# Sheet1.net
KiCad netlist of a schematic drawn in Altium Designer
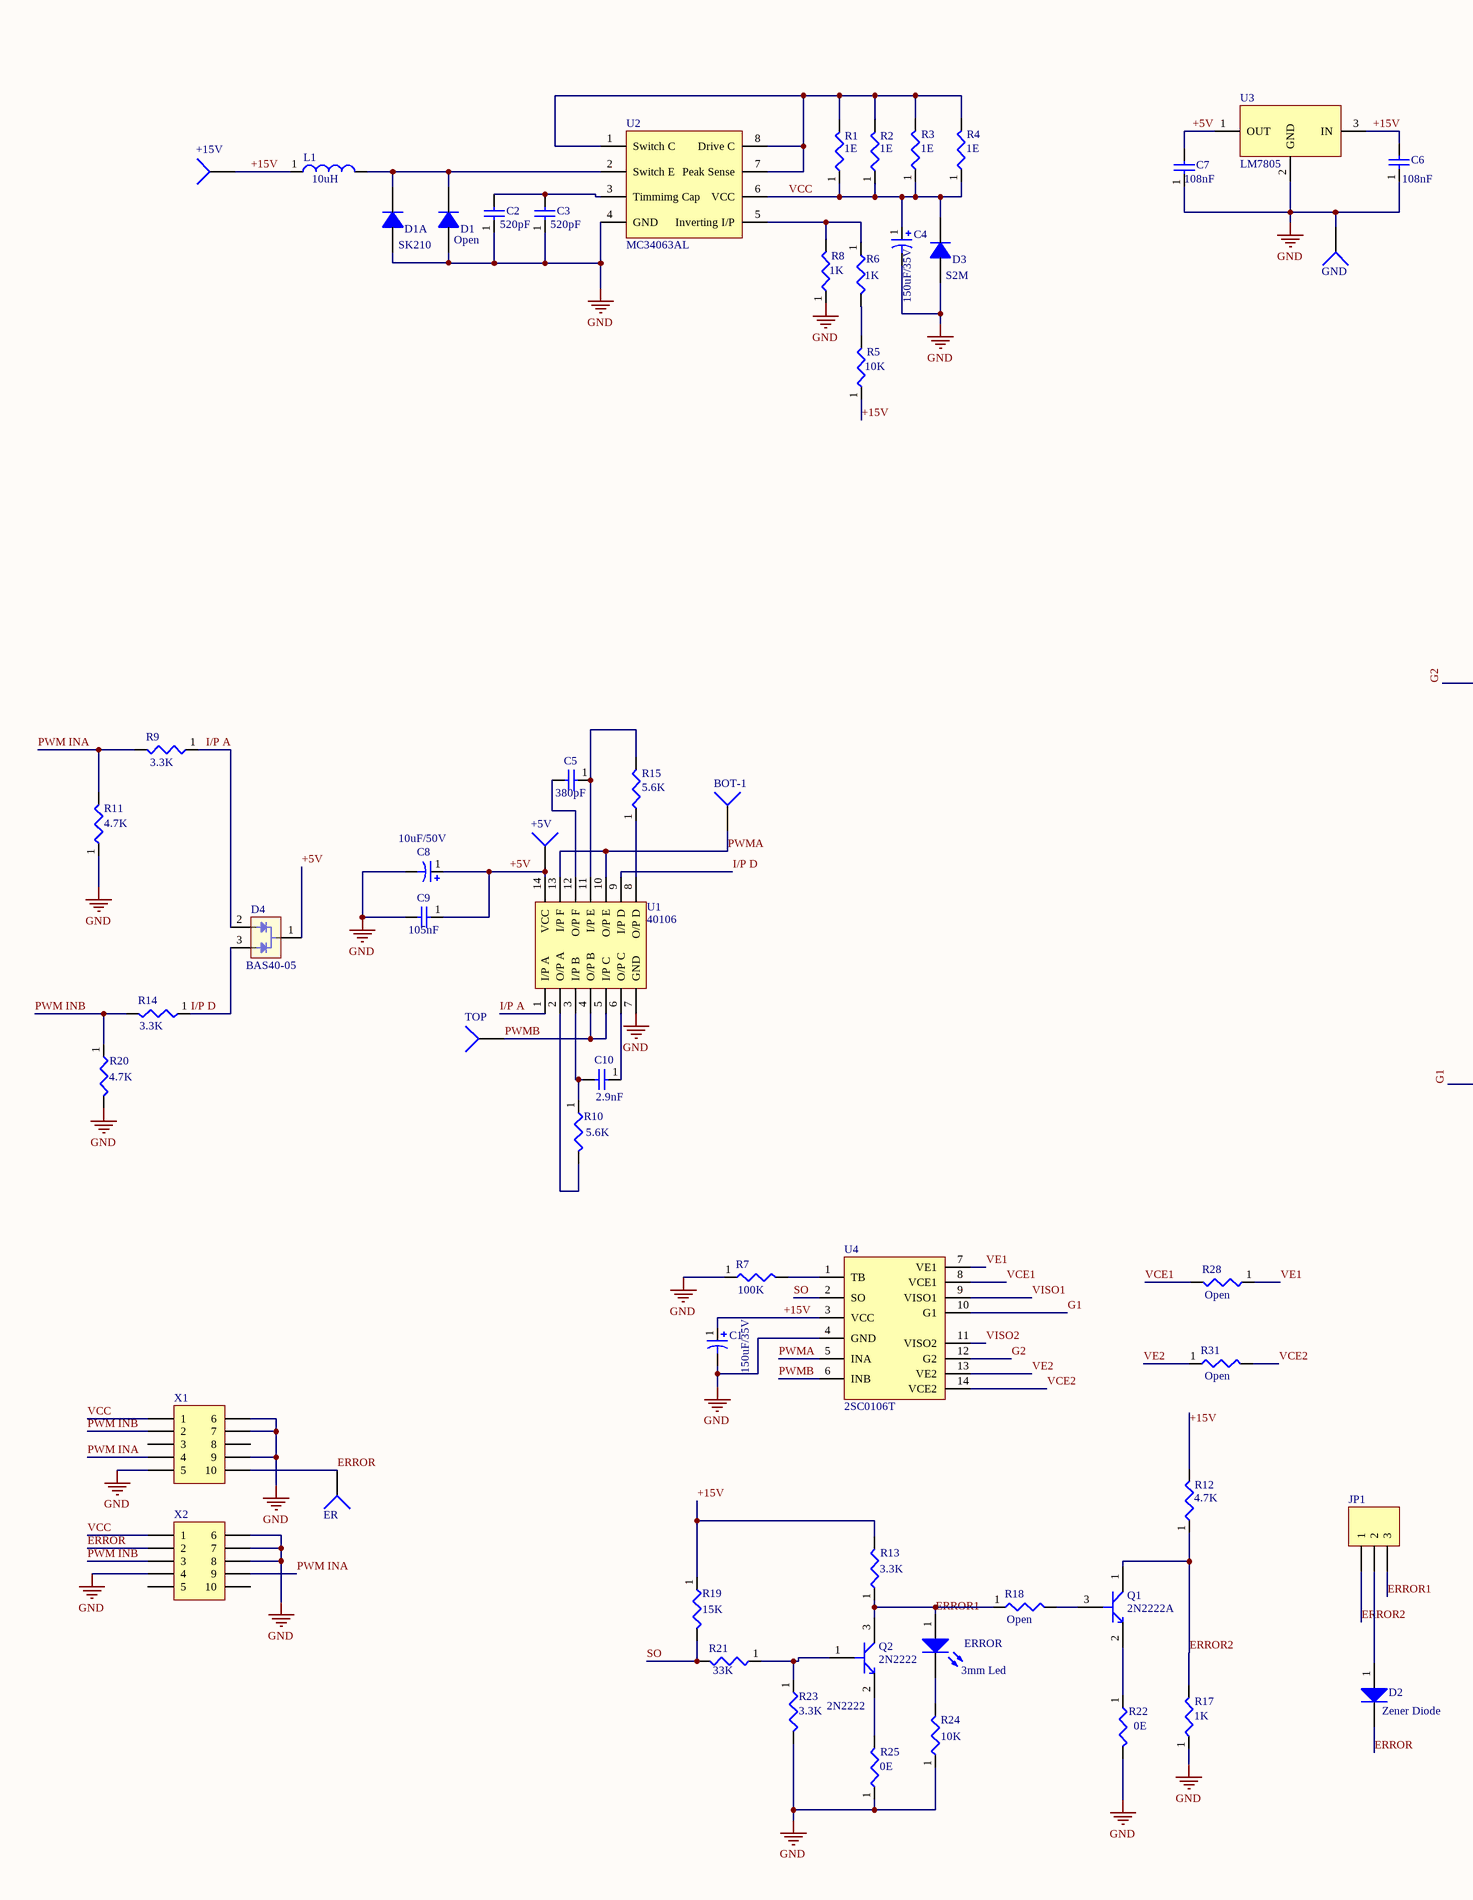
[diagram p0: Sheet1.SchDoc, left]
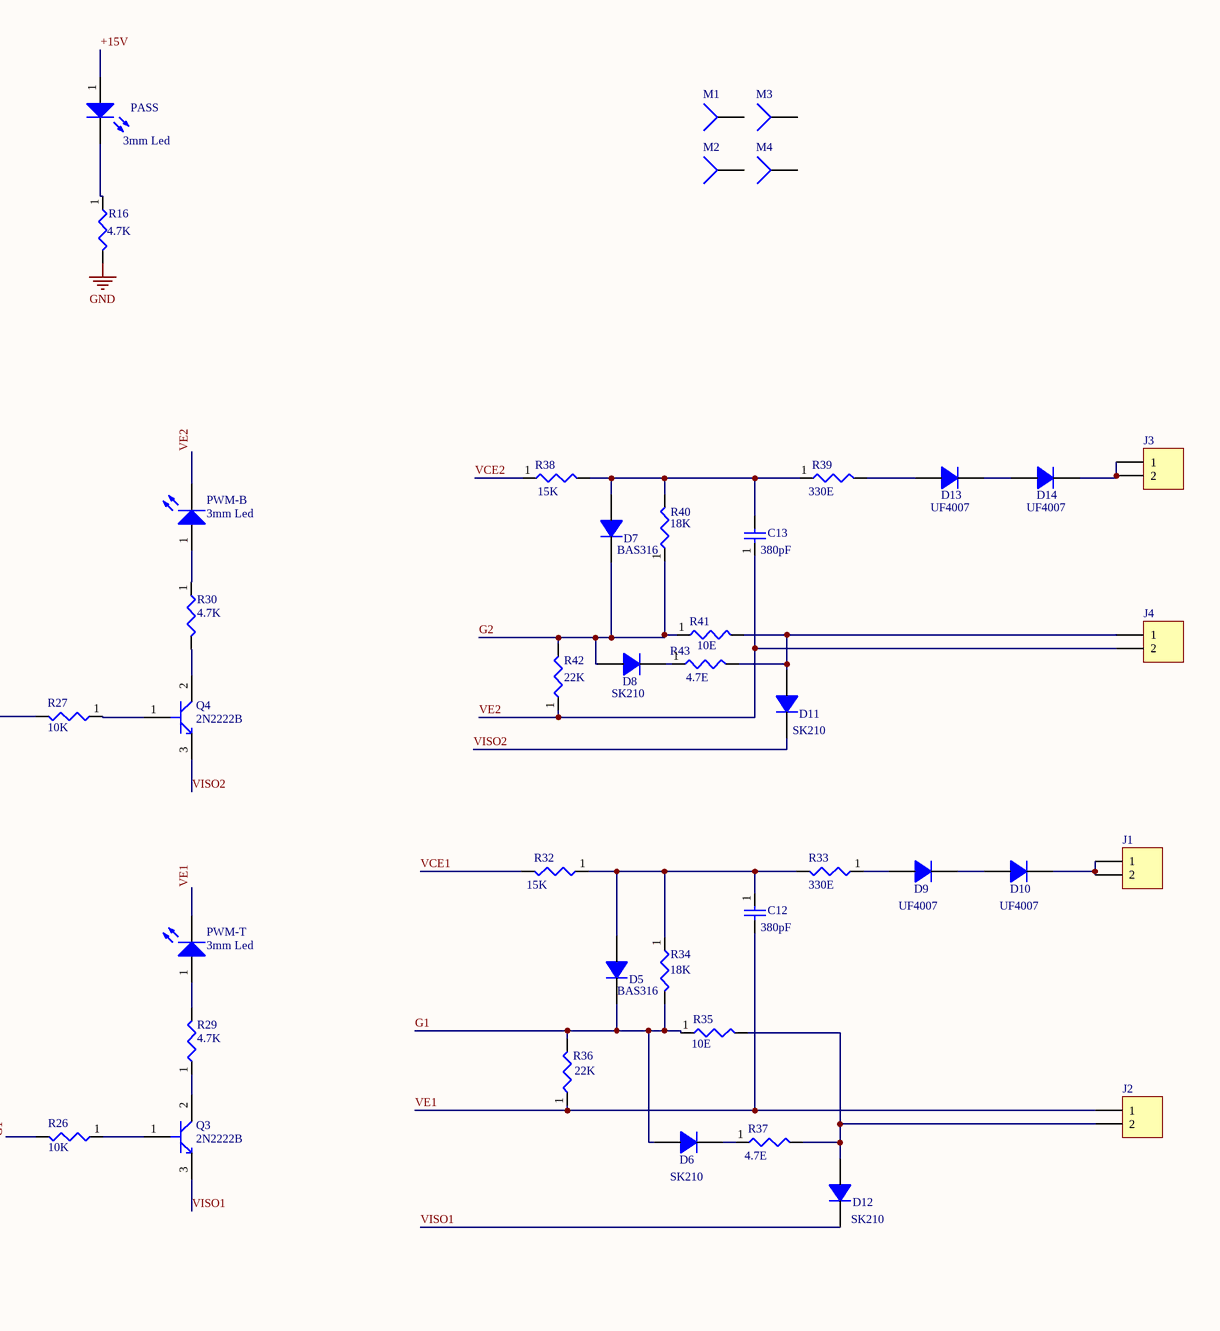
[diagram p1: Sheet1.SchDoc, right]

(export (version "E")
  (design (tool "Eeschema 10.0.6"))
  (components
    (comp (ref "+5V")
      (value "Socket")
      (footprint "tp")
      (fields (field (name "PUBLISHER") "Altium Limited"))
      (libsource (lib "Miscellaneous Connectors") (part "Socket"))
    )
    (comp (ref "+15V")
      (value "Socket")
      (footprint "tp")
      (fields (field (name "PUBLISHER") "Altium Limited"))
      (libsource (lib "Miscellaneous Connectors") (part "Socket"))
    )
    (comp (ref "BOT-1")
      (value "Socket")
      (footprint "tp")
      (fields (field (name "PUBLISHER") "Altium Limited"))
      (libsource (lib "Miscellaneous Connectors") (part "Socket"))
    )
    (comp (ref "C1")
      (value "150uF/35V")
      (footprint "10 mm Elco")
      (description "Polarized Capacitor (Radial)")
      (fields (field (name "Comment") "Cap Pol1") (field (name "PUBLISHER") "Altium Limited"))
      (libsource (lib "Miscellaneous Devices") (part "Cap Pol1"))
    )
    (comp (ref "C2")
      (value "520pF")
      (footprint "RESC0805-1206")
      (description "Capacitor")
      (fields (field (name "Comment") "Cap") (field (name "PUBLISHER") "Altium Limited"))
      (libsource (lib "Miscellaneous Devices") (part "Cap"))
    )
    (comp (ref "C3")
      (value "520pF")
      (footprint "RESC0805-1206")
      (description "Capacitor")
      (fields (field (name "Comment") "Cap") (field (name "PUBLISHER") "Altium Limited"))
      (libsource (lib "Miscellaneous Devices") (part "Cap"))
    )
    (comp (ref "C4")
      (value "150uF/35V")
      (footprint "10 mm Elco")
      (description "Polarized Capacitor (Radial)")
      (fields (field (name "Comment") "Cap Pol1") (field (name "PUBLISHER") "Altium Limited"))
      (libsource (lib "Miscellaneous Devices") (part "Cap Pol1"))
    )
    (comp (ref "C5")
      (value "380pF")
      (footprint "RESC0805-1206")
      (description "Capacitor")
      (fields (field (name "Comment") "Cap") (field (name "PUBLISHER") "Altium Limited"))
      (libsource (lib "Miscellaneous Devices") (part "Cap"))
    )
    (comp (ref "C6")
      (value "108nF")
      (footprint "RESC0805-1206")
      (description "Capacitor")
      (fields (field (name "Comment") "Cap") (field (name "PUBLISHER") "Altium Limited"))
      (libsource (lib "Miscellaneous Devices") (part "Cap"))
    )
    (comp (ref "C7")
      (value "108nF")
      (footprint "RESC0805-1206")
      (description "Capacitor")
      (fields (field (name "Comment") "Cap") (field (name "PUBLISHER") "Altium Limited"))
      (libsource (lib "Miscellaneous Devices") (part "Cap"))
    )
    (comp (ref "C8")
      (value "10uF/50V")
      (footprint "elco cap")
      (description "Polarized Capacitor (Radial)")
      (fields (field (name "Comment") "Cap Pol1") (field (name "PUBLISHER") "Altium Limited"))
      (libsource (lib "Miscellaneous Devices") (part "Cap Pol1"))
    )
    (comp (ref "C9")
      (value "105nF")
      (footprint "RESC0805-1206")
      (description "Capacitor")
      (fields (field (name "Comment") "Cap") (field (name "PUBLISHER") "Altium Limited"))
      (libsource (lib "Miscellaneous Devices") (part "Cap"))
    )
    (comp (ref "C10")
      (value "2.9nF")
      (footprint "RESC0805-1206")
      (description "Capacitor")
      (fields (field (name "Comment") "Cap") (field (name "PUBLISHER") "Altium Limited"))
      (libsource (lib "Miscellaneous Devices") (part "Cap"))
    )
    (comp (ref "C12")
      (value "380pF")
      (footprint "RESC0805-1206")
      (description "Capacitor")
      (fields (field (name "Comment") "Cap") (field (name "PUBLISHER") "Altium Limited"))
      (libsource (lib "Miscellaneous Devices") (part "Cap"))
    )
    (comp (ref "C13")
      (value "380pF")
      (footprint "RESC0805-1206")
      (description "Capacitor")
      (fields (field (name "Comment") "Cap") (field (name "PUBLISHER") "Altium Limited"))
      (libsource (lib "Miscellaneous Devices") (part "Cap"))
    )
    (comp (ref "D1")
      (value "Open")
      (footprint "Diode")
      (fields (field (name "Comment") "Diode"))
      (libsource (lib "Schlib1") (part "Diode"))
    )
    (comp (ref "D1A")
      (value "SK210")
      (footprint "smb")
      (fields (field (name "Comment") "Diode"))
      (libsource (lib "Schlib1") (part "Diode"))
    )
    (comp (ref "D2")
      (value "Zener Diode")
      (footprint "1206 diode")
      (description "Default Diode")
      (fields (field (name "Comment") "Diode") (field (name "PUBLISHER") "Altium Limited"))
      (libsource (lib "Miscellaneous Devices") (part "Diode"))
    )
    (comp (ref "D3")
      (value "S2M")
      (footprint "smb")
      (fields (field (name "Comment") "Diode"))
      (libsource (lib "Schlib1") (part "Diode"))
    )
    (comp (ref "D4") (value "BAS40-05") (footprint "SOT23_N") (libsource (lib "Schlib1") (part "BAS40-05")))
    (comp (ref "D5")
      (value "BAS316")
      (footprint "smd diode")
      (fields (field (name "Comment") "Diode"))
      (libsource (lib "Schlib1") (part "Diode"))
    )
    (comp (ref "D6")
      (value "SK210")
      (footprint "smb")
      (fields (field (name "Comment") "Diode"))
      (libsource (lib "Schlib1") (part "Diode"))
    )
    (comp (ref "D7")
      (value "BAS316")
      (footprint "smd diode")
      (fields (field (name "Comment") "Diode"))
      (libsource (lib "Schlib1") (part "Diode"))
    )
    (comp (ref "D8")
      (value "SK210")
      (footprint "smb")
      (fields (field (name "Comment") "Diode"))
      (libsource (lib "Schlib1") (part "Diode"))
    )
    (comp (ref "D9")
      (value "UF4007")
      (footprint "Diode")
      (fields (field (name "Comment") "Diode"))
      (libsource (lib "Schlib1") (part "Diode"))
    )
    (comp (ref "D10")
      (value "UF4007")
      (footprint "Diode")
      (fields (field (name "Comment") "Diode"))
      (libsource (lib "Schlib1") (part "Diode"))
    )
    (comp (ref "D11")
      (value "SK210")
      (footprint "smb")
      (fields (field (name "Comment") "Diode"))
      (libsource (lib "Schlib1") (part "Diode"))
    )
    (comp (ref "D12")
      (value "SK210")
      (footprint "smb")
      (fields (field (name "Comment") "Diode"))
      (libsource (lib "Schlib1") (part "Diode"))
    )
    (comp (ref "D13")
      (value "UF4007")
      (footprint "Diode")
      (fields (field (name "Comment") "Diode"))
      (libsource (lib "Schlib1") (part "Diode"))
    )
    (comp (ref "D14")
      (value "UF4007")
      (footprint "Diode")
      (fields (field (name "Comment") "Diode"))
      (libsource (lib "Schlib1") (part "Diode"))
    )
    (comp (ref "ER")
      (value "Socket")
      (footprint "tp")
      (fields (field (name "PUBLISHER") "Altium Limited"))
      (libsource (lib "Miscellaneous Connectors") (part "Socket"))
    )
    (comp (ref "ERROR")
      (value "3mm Led")
      (footprint "led")
      (description "Typical INFRARED GaAs LED")
      (fields (field (name "Comment") "LED0") (field (name "PUBLISHER") "Altium Limited"))
      (libsource (lib "Miscellaneous Devices") (part "LED0"))
    )
    (comp (ref "GND")
      (value "Socket")
      (footprint "tp")
      (fields (field (name "PUBLISHER") "Altium Limited"))
      (libsource (lib "Miscellaneous Connectors") (part "Socket"))
    )
    (comp (ref "J1")
      (value "Header 2")
      (footprint "2 pin con")
      (description "Header, 2-Pin")
      (fields (field (name "PUBLISHER") "Altium Limited"))
      (libsource (lib "Miscellaneous Connectors") (part "Header 2"))
    )
    (comp (ref "J2")
      (value "Header 2")
      (footprint "2 pin con")
      (description "Header, 2-Pin")
      (fields (field (name "PUBLISHER") "Altium Limited"))
      (libsource (lib "Miscellaneous Connectors") (part "Header 2"))
    )
    (comp (ref "J3")
      (value "Header 2")
      (footprint "2 pin con")
      (description "Header, 2-Pin")
      (fields (field (name "PUBLISHER") "Altium Limited"))
      (libsource (lib "Miscellaneous Connectors") (part "Header 2"))
    )
    (comp (ref "J4")
      (value "Header 2")
      (footprint "2 pin con")
      (description "Header, 2-Pin")
      (fields (field (name "PUBLISHER") "Altium Limited"))
      (libsource (lib "Miscellaneous Connectors") (part "Header 2"))
    )
    (comp (ref "JP1")
      (value "Header 3")
      (footprint "3 pin con")
      (description "Header, 3-Pin")
      (fields (field (name "PUBLISHER") "Altium Limited"))
      (libsource (lib "Miscellaneous Connectors") (part "Header 3"))
    )
    (comp (ref "L1")
      (value "10uH")
      (footprint "INDUCTOR")
      (description "Inductor")
      (fields (field (name "PUBLISHER") "Altium Limited"))
      (libsource (lib "Miscellaneous Devices") (part "Inductor"))
    )
    (comp (ref "M1")
      (value "Socket")
      (footprint "Mounting Hole")
      (fields (field (name "PUBLISHER") "Altium Limited"))
      (libsource (lib "Miscellaneous Connectors") (part "Socket"))
    )
    (comp (ref "M2")
      (value "Socket")
      (footprint "Mounting Hole")
      (fields (field (name "PUBLISHER") "Altium Limited"))
      (libsource (lib "Miscellaneous Connectors") (part "Socket"))
    )
    (comp (ref "M3")
      (value "Socket")
      (footprint "Mounting Hole")
      (fields (field (name "PUBLISHER") "Altium Limited"))
      (libsource (lib "Miscellaneous Connectors") (part "Socket"))
    )
    (comp (ref "M4")
      (value "Socket")
      (footprint "Mounting Hole")
      (fields (field (name "PUBLISHER") "Altium Limited"))
      (libsource (lib "Miscellaneous Connectors") (part "Socket"))
    )
    (comp (ref "PASS")
      (value "3mm Led")
      (footprint "led")
      (description "Typical INFRARED GaAs LED")
      (fields (field (name "Comment") "LED0") (field (name "PUBLISHER") "Altium Limited"))
      (libsource (lib "Miscellaneous Devices") (part "LED0"))
    )
    (comp (ref "PWM-B")
      (value "3mm Led")
      (footprint "led")
      (description "Typical INFRARED GaAs LED")
      (fields (field (name "Comment") "LED0") (field (name "PUBLISHER") "Altium Limited"))
      (libsource (lib "Miscellaneous Devices") (part "LED0"))
    )
    (comp (ref "PWM-T")
      (value "3mm Led")
      (footprint "led")
      (description "Typical INFRARED GaAs LED")
      (fields (field (name "Comment") "LED0") (field (name "PUBLISHER") "Altium Limited"))
      (libsource (lib "Miscellaneous Devices") (part "LED0"))
    )
    (comp (ref "Q1") (value "2N2222A") (footprint "SOT23_N") (libsource (lib "Schlib1") (part "2N2222A")))
    (comp (ref "Q2")
      (value "2N2222")
      (footprint "SOT-23_N")
      (fields (field (name "ALTIUM_VALUE") "2N2222"))
      (libsource (lib "Schlib1") (part "2N2222"))
    )
    (comp (ref "Q3") (value "2N2222B") (footprint "SOT-23_N") (libsource (lib "Schlib1") (part "2N2222B")))
    (comp (ref "Q4") (value "2N2222B") (footprint "SOT-23_N") (libsource (lib "Schlib1") (part "2N2222B")))
    (comp (ref "R1")
      (value "1E")
      (footprint "RESC0805-1206")
      (description "Resistor")
      (fields (field (name "Comment") "Res3") (field (name "PUBLISHER") "Altium Limited"))
      (libsource (lib "Miscellaneous Devices") (part "Res3"))
    )
    (comp (ref "R2")
      (value "1E")
      (footprint "RESC0805-1206")
      (description "Resistor")
      (fields (field (name "Comment") "Res3") (field (name "PUBLISHER") "Altium Limited"))
      (libsource (lib "Miscellaneous Devices") (part "Res3"))
    )
    (comp (ref "R3")
      (value "1E")
      (footprint "RESC0805-1206")
      (description "Resistor")
      (fields (field (name "Comment") "Res3") (field (name "PUBLISHER") "Altium Limited"))
      (libsource (lib "Miscellaneous Devices") (part "Res3"))
    )
    (comp (ref "R4")
      (value "1E")
      (footprint "RESC0805-1206")
      (description "Resistor")
      (fields (field (name "Comment") "Res3") (field (name "PUBLISHER") "Altium Limited"))
      (libsource (lib "Miscellaneous Devices") (part "Res3"))
    )
    (comp (ref "R5")
      (value "10K")
      (footprint "RESC0805-1206")
      (description "Resistor")
      (fields (field (name "Comment") "Res3") (field (name "PUBLISHER") "Altium Limited"))
      (libsource (lib "Miscellaneous Devices") (part "Res3"))
    )
    (comp (ref "R6")
      (value "1K")
      (footprint "RESC0805-1206")
      (description "Resistor")
      (fields (field (name "Comment") "Res3") (field (name "PUBLISHER") "Altium Limited"))
      (libsource (lib "Miscellaneous Devices") (part "Res3"))
    )
    (comp (ref "R7")
      (value "100K")
      (footprint "RESC0805-1206")
      (description "Resistor")
      (fields (field (name "Comment") "Res3") (field (name "PUBLISHER") "Altium Limited"))
      (libsource (lib "Miscellaneous Devices") (part "Res3"))
    )
    (comp (ref "R8")
      (value "1K")
      (footprint "RESC0805-1206")
      (description "Resistor")
      (fields (field (name "Comment") "Res3") (field (name "PUBLISHER") "Altium Limited"))
      (libsource (lib "Miscellaneous Devices") (part "Res3"))
    )
    (comp (ref "R9")
      (value "3.3K")
      (footprint "RESC0805-1206")
      (description "Resistor")
      (fields (field (name "Comment") "Res3") (field (name "PUBLISHER") "Altium Limited"))
      (libsource (lib "Miscellaneous Devices") (part "Res3"))
    )
    (comp (ref "R10")
      (value "5.6K")
      (footprint "RESC0805-1206")
      (description "Resistor")
      (fields (field (name "Comment") "Res3") (field (name "PUBLISHER") "Altium Limited"))
      (libsource (lib "Miscellaneous Devices") (part "Res3"))
    )
    (comp (ref "R11")
      (value "4.7K")
      (footprint "RESC0805-1206")
      (description "Resistor")
      (fields (field (name "Comment") "Res3") (field (name "PUBLISHER") "Altium Limited"))
      (libsource (lib "Miscellaneous Devices") (part "Res3"))
    )
    (comp (ref "R12")
      (value "4.7K")
      (footprint "RESC0805-1206")
      (description "Resistor")
      (fields (field (name "Comment") "Res3") (field (name "PUBLISHER") "Altium Limited"))
      (libsource (lib "Miscellaneous Devices") (part "Res3"))
    )
    (comp (ref "R13")
      (value "3.3K")
      (footprint "RESC0805-1206")
      (description "Resistor")
      (fields (field (name "Comment") "Res3") (field (name "PUBLISHER") "Altium Limited"))
      (libsource (lib "Miscellaneous Devices") (part "Res3"))
    )
    (comp (ref "R14")
      (value "3.3K")
      (footprint "RESC0805-1206")
      (description "Resistor")
      (fields (field (name "Comment") "Res3") (field (name "PUBLISHER") "Altium Limited"))
      (libsource (lib "Miscellaneous Devices") (part "Res3"))
    )
    (comp (ref "R15")
      (value "5.6K")
      (footprint "RESC0805-1206")
      (description "Resistor")
      (fields (field (name "Comment") "Res3") (field (name "PUBLISHER") "Altium Limited"))
      (libsource (lib "Miscellaneous Devices") (part "Res3"))
    )
    (comp (ref "R16")
      (value "4.7K")
      (footprint "RESC0805-1206")
      (description "Resistor")
      (fields (field (name "Comment") "Res3") (field (name "PUBLISHER") "Altium Limited"))
      (libsource (lib "Miscellaneous Devices") (part "Res3"))
    )
    (comp (ref "R17")
      (value "1K")
      (footprint "RESC0805-1206")
      (description "Resistor")
      (fields (field (name "Comment") "Res3") (field (name "PUBLISHER") "Altium Limited"))
      (libsource (lib "Miscellaneous Devices") (part "Res3"))
    )
    (comp (ref "R18")
      (value "Open")
      (footprint "RESC0805-1206")
      (description "Resistor")
      (fields (field (name "Comment") "Res3") (field (name "PUBLISHER") "Altium Limited"))
      (libsource (lib "Miscellaneous Devices") (part "Res3"))
    )
    (comp (ref "R19")
      (value "15K")
      (footprint "RESC0805-1206")
      (description "Resistor")
      (fields (field (name "Comment") "Res3") (field (name "PUBLISHER") "Altium Limited"))
      (libsource (lib "Miscellaneous Devices") (part "Res3"))
    )
    (comp (ref "R20")
      (value "4.7K")
      (footprint "RESC0805-1206")
      (description "Resistor")
      (fields (field (name "Comment") "Res3") (field (name "PUBLISHER") "Altium Limited"))
      (libsource (lib "Miscellaneous Devices") (part "Res3"))
    )
    (comp (ref "R21")
      (value "33K")
      (footprint "RESC0805-1206")
      (description "Resistor")
      (fields (field (name "Comment") "Res3") (field (name "PUBLISHER") "Altium Limited"))
      (libsource (lib "Miscellaneous Devices") (part "Res3"))
    )
    (comp (ref "R22")
      (value "0E")
      (footprint "RESC0805-1206")
      (description "Resistor")
      (fields (field (name "Comment") "Res3") (field (name "PUBLISHER") "Altium Limited"))
      (libsource (lib "Miscellaneous Devices") (part "Res3"))
    )
    (comp (ref "R23")
      (value "3.3K")
      (footprint "RESC0805-1206")
      (description "Resistor")
      (fields (field (name "Comment") "Res3") (field (name "PUBLISHER") "Altium Limited"))
      (libsource (lib "Miscellaneous Devices") (part "Res3"))
    )
    (comp (ref "R24")
      (value "10K")
      (footprint "RESC0805-1206")
      (description "Resistor")
      (fields (field (name "Comment") "Res3") (field (name "PUBLISHER") "Altium Limited"))
      (libsource (lib "Miscellaneous Devices") (part "Res3"))
    )
    (comp (ref "R25")
      (value "0E")
      (footprint "RESC0805-1206")
      (description "Resistor")
      (fields (field (name "Comment") "Res3") (field (name "PUBLISHER") "Altium Limited"))
      (libsource (lib "Miscellaneous Devices") (part "Res3"))
    )
    (comp (ref "R26")
      (value "10K")
      (footprint "RESC0805-1206")
      (description "Resistor")
      (fields (field (name "Comment") "Res3") (field (name "PUBLISHER") "Altium Limited"))
      (libsource (lib "Miscellaneous Devices") (part "Res3"))
    )
    (comp (ref "R27")
      (value "10K")
      (footprint "RESC0805-1206")
      (description "Resistor")
      (fields (field (name "Comment") "Res3") (field (name "PUBLISHER") "Altium Limited"))
      (libsource (lib "Miscellaneous Devices") (part "Res3"))
    )
    (comp (ref "R28")
      (value "Open")
      (footprint "RESC0805-1206")
      (description "Resistor")
      (fields (field (name "Comment") "Res3") (field (name "PUBLISHER") "Altium Limited"))
      (libsource (lib "Miscellaneous Devices") (part "Res3"))
    )
    (comp (ref "R29")
      (value "4.7K")
      (footprint "RESC0805-1206")
      (description "Resistor")
      (fields (field (name "Comment") "Res3") (field (name "PUBLISHER") "Altium Limited"))
      (libsource (lib "Miscellaneous Devices") (part "Res3"))
    )
    (comp (ref "R30")
      (value "4.7K")
      (footprint "RESC0805-1206")
      (description "Resistor")
      (fields (field (name "Comment") "Res3") (field (name "PUBLISHER") "Altium Limited"))
      (libsource (lib "Miscellaneous Devices") (part "Res3"))
    )
    (comp (ref "R31")
      (value "Open")
      (footprint "RESC0805-1206")
      (description "Resistor")
      (fields (field (name "Comment") "Res3") (field (name "PUBLISHER") "Altium Limited"))
      (libsource (lib "Miscellaneous Devices") (part "Res3"))
    )
    (comp (ref "R32")
      (value "15K")
      (footprint "RESC0805-1206")
      (description "Resistor")
      (fields (field (name "Comment") "Res3") (field (name "PUBLISHER") "Altium Limited"))
      (libsource (lib "Miscellaneous Devices") (part "Res3"))
    )
    (comp (ref "R33")
      (value "330E")
      (footprint "RESC0805-1206")
      (description "Resistor")
      (fields (field (name "Comment") "Res3") (field (name "PUBLISHER") "Altium Limited"))
      (libsource (lib "Miscellaneous Devices") (part "Res3"))
    )
    (comp (ref "R34")
      (value "18K")
      (footprint "RESC0805-1206")
      (description "Resistor")
      (fields (field (name "Comment") "Res3") (field (name "PUBLISHER") "Altium Limited"))
      (libsource (lib "Miscellaneous Devices") (part "Res3"))
    )
    (comp (ref "R35")
      (value "10E")
      (footprint "2W Res")
      (description "Resistor")
      (fields (field (name "Comment") "Res3") (field (name "PUBLISHER") "Altium Limited"))
      (libsource (lib "Miscellaneous Devices") (part "Res3"))
    )
    (comp (ref "R36")
      (value "22K")
      (footprint "RESC0805-1206")
      (description "Resistor")
      (fields (field (name "Comment") "Res3") (field (name "PUBLISHER") "Altium Limited"))
      (libsource (lib "Miscellaneous Devices") (part "Res3"))
    )
    (comp (ref "R37")
      (value "4.7E")
      (footprint "2W Res")
      (description "Resistor")
      (fields (field (name "Comment") "Res3") (field (name "PUBLISHER") "Altium Limited"))
      (libsource (lib "Miscellaneous Devices") (part "Res3"))
    )
    (comp (ref "R38")
      (value "15K")
      (footprint "RESC0805-1206")
      (description "Resistor")
      (fields (field (name "Comment") "Res3") (field (name "PUBLISHER") "Altium Limited"))
      (libsource (lib "Miscellaneous Devices") (part "Res3"))
    )
    (comp (ref "R39")
      (value "330E")
      (footprint "RESC0805-1206")
      (description "Resistor")
      (fields (field (name "Comment") "Res3") (field (name "PUBLISHER") "Altium Limited"))
      (libsource (lib "Miscellaneous Devices") (part "Res3"))
    )
    (comp (ref "R40")
      (value "18K")
      (footprint "RESC0805-1206")
      (description "Resistor")
      (fields (field (name "Comment") "Res3") (field (name "PUBLISHER") "Altium Limited"))
      (libsource (lib "Miscellaneous Devices") (part "Res3"))
    )
    (comp (ref "R41")
      (value "10E")
      (footprint "2W Res")
      (description "Resistor")
      (fields (field (name "Comment") "Res3") (field (name "PUBLISHER") "Altium Limited"))
      (libsource (lib "Miscellaneous Devices") (part "Res3"))
    )
    (comp (ref "R42")
      (value "22K")
      (footprint "RESC0805-1206")
      (description "Resistor")
      (fields (field (name "Comment") "Res3") (field (name "PUBLISHER") "Altium Limited"))
      (libsource (lib "Miscellaneous Devices") (part "Res3"))
    )
    (comp (ref "R43")
      (value "4.7E")
      (footprint "2W Res")
      (description "Resistor")
      (fields (field (name "Comment") "Res3") (field (name "PUBLISHER") "Altium Limited"))
      (libsource (lib "Miscellaneous Devices") (part "Res3"))
    )
    (comp (ref "TOP")
      (value "Socket")
      (footprint "tp")
      (fields (field (name "PUBLISHER") "Altium Limited"))
      (libsource (lib "Miscellaneous Connectors") (part "Socket"))
    )
    (comp (ref "U1")
      (value "40106")
      (footprint "sop14")
      (fields (field (name "Comment") "CD40106"))
      (libsource (lib "Schlib1") (part "CD40106"))
    )
    (comp (ref "U2") (value "MC34063AL") (libsource (lib "Schlib1") (part "MC34063AL")))
    (comp (ref "U3") (value "LM7805") (libsource (lib "Schlib1") (part "LM7805")))
    (comp (ref "U4") (value "2SC0106T") (footprint "14 pin ic") (libsource (lib "Schlib1") (part "2SC0106T")))
    (comp (ref "X1")
      (value "Header 5X2A")
      (footprint "10 pin con")
      (description "Header, 5-Pin, Dual row")
      (fields (field (name "PUBLISHER") "Altium Limited"))
      (libsource (lib "Miscellaneous Connectors") (part "Header 5X2A"))
    )
    (comp (ref "X2")
      (value "Header 5X2A")
      (footprint "X2 CON")
      (description "Header, 5-Pin, Dual row")
      (fields (field (name "PUBLISHER") "Altium Limited"))
      (libsource (lib "Miscellaneous Connectors") (part "Header 5X2A"))
    )
  )
  (nets
    (net (code "1") (name "/+5V") (class "Default")
      (node (ref "+5V") (pin "1") (pinfunction "1_1") (pintype "passive"))
      (node (ref "C7") (pin "2") (pinfunction "2_2") (pintype "passive"))
      (node (ref "C8") (pin "1") (pinfunction "1_1") (pintype "passive"))
      (node (ref "C9") (pin "1") (pinfunction "1_1") (pintype "passive"))
      (node (ref "D4") (pin "1") (pinfunction "1_1") (pintype "passive"))
      (node (ref "U1") (pin "14") (pinfunction "VCC_14") (pintype "passive"))
      (node (ref "U3") (pin "1") (pinfunction "OUT_1") (pintype "passive"))
    )
    (net (code "2") (name "/+15V") (class "Default")
      (node (ref "+15V") (pin "1") (pinfunction "1_1") (pintype "passive"))
      (node (ref "C1") (pin "1") (pinfunction "1_1") (pintype "passive"))
      (node (ref "C6") (pin "2") (pinfunction "2_2") (pintype "passive"))
      (node (ref "L1") (pin "1") (pinfunction "1_1") (pintype "passive"))
      (node (ref "PASS") (pin "1") (pinfunction "A_1") (pintype "passive"))
      (node (ref "R12") (pin "2") (pinfunction "2_2") (pintype "passive"))
      (node (ref "R13") (pin "2") (pinfunction "2_2") (pintype "passive"))
      (node (ref "R19") (pin "1") (pinfunction "1_1") (pintype "passive"))
      (node (ref "R5") (pin "1") (pinfunction "1_1") (pintype "passive"))
      (node (ref "U3") (pin "3") (pinfunction "IN_3") (pintype "passive"))
      (node (ref "U4") (pin "3") (pinfunction "VCC_3") (pintype "passive"))
    )
    (net (code "3") (name "/ERROR") (class "Default")
      (node (ref "D2") (pin "2") (pinfunction "K_2") (pintype "passive"))
      (node (ref "ER") (pin "1") (pinfunction "1_1") (pintype "passive"))
      (node (ref "X1") (pin "10") (pinfunction "10_10") (pintype "passive"))
      (node (ref "X2") (pin "2") (pinfunction "2_2") (pintype "passive"))
    )
    (net (code "4") (name "/ERROR1") (class "Default")
      (node (ref "ERROR") (pin "1") (pinfunction "A_1") (pintype "passive"))
      (node (ref "JP1") (pin "3") (pinfunction "3_3") (pintype "passive"))
      (node (ref "Q2") (pin "3") (pinfunction "3_3") (pintype "passive"))
      (node (ref "R13") (pin "1") (pinfunction "1_1") (pintype "passive"))
      (node (ref "R18") (pin "1") (pinfunction "1_1") (pintype "passive"))
    )
    (net (code "5") (name "/ERROR2") (class "Default")
      (node (ref "JP1") (pin "1") (pinfunction "1_1") (pintype "passive"))
      (node (ref "Q1") (pin "1") (pinfunction "1_1") (pintype "passive"))
      (node (ref "R12") (pin "1") (pinfunction "1_1") (pintype "passive"))
      (node (ref "R17") (pin "2") (pinfunction "2_2") (pintype "passive"))
    )
    (net (code "6") (name "/G1") (class "Default")
      (node (ref "D5") (pin "1") (pinfunction "1_1") (pintype "passive"))
      (node (ref "D6") (pin "2") (pinfunction "2_2") (pintype "passive"))
      (node (ref "R26") (pin "2") (pinfunction "2_2") (pintype "passive"))
      (node (ref "R34") (pin "2") (pinfunction "2_2") (pintype "passive"))
      (node (ref "R35") (pin "1") (pinfunction "1_1") (pintype "passive"))
      (node (ref "R36") (pin "2") (pinfunction "2_2") (pintype "passive"))
      (node (ref "U4") (pin "10") (pinfunction "G1_10") (pintype "passive"))
    )
    (net (code "7") (name "/G2") (class "Default")
      (node (ref "D7") (pin "1") (pinfunction "1_1") (pintype "passive"))
      (node (ref "D8") (pin "2") (pinfunction "2_2") (pintype "passive"))
      (node (ref "R27") (pin "2") (pinfunction "2_2") (pintype "passive"))
      (node (ref "R40") (pin "1") (pinfunction "1_1") (pintype "passive"))
      (node (ref "R41") (pin "1") (pinfunction "1_1") (pintype "passive"))
      (node (ref "R42") (pin "2") (pinfunction "2_2") (pintype "passive"))
      (node (ref "U4") (pin "12") (pinfunction "G2_12") (pintype "passive"))
    )
    (net (code "8") (name "/I{slash}P A") (class "Default")
      (node (ref "D4") (pin "2") (pinfunction "2_2") (pintype "passive"))
      (node (ref "R9") (pin "1") (pinfunction "1_1") (pintype "passive"))
      (node (ref "U1") (pin "1") (pinfunction "I/P_A_1") (pintype "passive"))
    )
    (net (code "9") (name "/I{slash}P D") (class "Default")
      (node (ref "D4") (pin "3") (pinfunction "3_3") (pintype "passive"))
      (node (ref "R14") (pin "1") (pinfunction "1_1") (pintype "passive"))
      (node (ref "U1") (pin "9") (pinfunction "I/P_D_9") (pintype "passive"))
    )
    (net (code "10") (name "/PWM INA") (class "Default")
      (node (ref "R11") (pin "2") (pinfunction "2_2") (pintype "passive"))
      (node (ref "R9") (pin "2") (pinfunction "2_2") (pintype "passive"))
      (node (ref "X1") (pin "4") (pinfunction "4_4") (pintype "passive"))
      (node (ref "X2") (pin "9") (pinfunction "9_9") (pintype "passive"))
    )
    (net (code "11") (name "/PWM INB") (class "Default")
      (node (ref "R14") (pin "2") (pinfunction "2_2") (pintype "passive"))
      (node (ref "R20") (pin "1") (pinfunction "1_1") (pintype "passive"))
      (node (ref "X1") (pin "2") (pinfunction "2_2") (pintype "passive"))
      (node (ref "X2") (pin "3") (pinfunction "3_3") (pintype "passive"))
    )
    (net (code "12") (name "/PWMA") (class "Default")
      (node (ref "BOT-1") (pin "1") (pinfunction "1_1") (pintype "passive"))
      (node (ref "U1") (pin "10") (pinfunction "O/P_E_10") (pintype "passive"))
      (node (ref "U1") (pin "13") (pinfunction "I/P_F_13") (pintype "passive"))
      (node (ref "U4") (pin "5") (pinfunction "INA_5") (pintype "passive"))
    )
    (net (code "13") (name "/PWMB") (class "Default")
      (node (ref "TOP") (pin "1") (pinfunction "1_1") (pintype "passive"))
      (node (ref "U1") (pin "4") (pinfunction "O/P_B_4") (pintype "passive"))
      (node (ref "U1") (pin "5") (pinfunction "I/P_C_5") (pintype "passive"))
      (node (ref "U4") (pin "6") (pinfunction "INB_6") (pintype "passive"))
    )
    (net (code "14") (name "/SO") (class "Default")
      (node (ref "R19") (pin "2") (pinfunction "2_2") (pintype "passive"))
      (node (ref "R21") (pin "2") (pinfunction "2_2") (pintype "passive"))
      (node (ref "U4") (pin "2") (pinfunction "SO_2") (pintype "passive"))
    )
    (net (code "15") (name "/VCC") (class "Default")
      (node (ref "C4") (pin "1") (pinfunction "1_1") (pintype "passive"))
      (node (ref "D3") (pin "1") (pinfunction "1_1") (pintype "passive"))
      (node (ref "R1") (pin "1") (pinfunction "1_1") (pintype "passive"))
      (node (ref "R2") (pin "1") (pinfunction "1_1") (pintype "passive"))
      (node (ref "R3") (pin "1") (pinfunction "1_1") (pintype "passive"))
      (node (ref "R4") (pin "1") (pinfunction "1_1") (pintype "passive"))
      (node (ref "U2") (pin "6") (pinfunction "VCC_6") (pintype "passive"))
      (node (ref "X1") (pin "1") (pinfunction "1_1") (pintype "passive"))
      (node (ref "X2") (pin "1") (pinfunction "1_1") (pintype "passive"))
    )
    (net (code "16") (name "/VCE1") (class "Default")
      (node (ref "R28") (pin "2") (pinfunction "2_2") (pintype "passive"))
      (node (ref "R32") (pin "2") (pinfunction "2_2") (pintype "passive"))
      (node (ref "U4") (pin "8") (pinfunction "VCE1_8") (pintype "passive"))
    )
    (net (code "17") (name "/VCE2") (class "Default")
      (node (ref "R31") (pin "2") (pinfunction "2_2") (pintype "passive"))
      (node (ref "R38") (pin "1") (pinfunction "1_1") (pintype "passive"))
      (node (ref "U4") (pin "14") (pinfunction "VCE2_14") (pintype "passive"))
    )
    (net (code "18") (name "/VE1") (class "Default")
      (node (ref "C12") (pin "2") (pinfunction "2_2") (pintype "passive"))
      (node (ref "J2") (pin "1") (pinfunction "1_1") (pintype "passive"))
      (node (ref "PWM-T") (pin "2") (pinfunction "K_2") (pintype "passive"))
      (node (ref "R28") (pin "1") (pinfunction "1_1") (pintype "passive"))
      (node (ref "R36") (pin "1") (pinfunction "1_1") (pintype "passive"))
      (node (ref "U4") (pin "7") (pinfunction "VE1_7") (pintype "passive"))
    )
    (net (code "19") (name "/VE2") (class "Default")
      (node (ref "C13") (pin "1") (pinfunction "1_1") (pintype "passive"))
      (node (ref "J4") (pin "2") (pinfunction "2_2") (pintype "passive"))
      (node (ref "PWM-B") (pin "2") (pinfunction "K_2") (pintype "passive"))
      (node (ref "R31") (pin "1") (pinfunction "1_1") (pintype "passive"))
      (node (ref "R42") (pin "1") (pinfunction "1_1") (pintype "passive"))
      (node (ref "U4") (pin "13") (pinfunction "VE2_13") (pintype "passive"))
    )
    (net (code "20") (name "/VISO1") (class "Default")
      (node (ref "D12") (pin "1") (pinfunction "1_1") (pintype "passive"))
      (node (ref "Q3") (pin "3") (pinfunction "3_3") (pintype "passive"))
      (node (ref "U4") (pin "9") (pinfunction "VISO1_9") (pintype "passive"))
    )
    (net (code "21") (name "/VISO2") (class "Default")
      (node (ref "D11") (pin "1") (pinfunction "1_1") (pintype "passive"))
      (node (ref "Q4") (pin "3") (pinfunction "3_3") (pintype "passive"))
      (node (ref "U4") (pin "11") (pinfunction "VISO2_11") (pintype "passive"))
    )
    (net (code "22") (name "GND") (class "Default")
      (node (ref "C1") (pin "2") (pinfunction "2_2") (pintype "passive"))
      (node (ref "C2") (pin "1") (pinfunction "1_1") (pintype "passive"))
      (node (ref "C3") (pin "1") (pinfunction "1_1") (pintype "passive"))
      (node (ref "C4") (pin "2") (pinfunction "2_2") (pintype "passive"))
      (node (ref "C6") (pin "1") (pinfunction "1_1") (pintype "passive"))
      (node (ref "C7") (pin "1") (pinfunction "1_1") (pintype "passive"))
      (node (ref "C8") (pin "2") (pinfunction "2_2") (pintype "passive"))
      (node (ref "C9") (pin "2") (pinfunction "2_2") (pintype "passive"))
      (node (ref "D1") (pin "2") (pinfunction "2_2") (pintype "passive"))
      (node (ref "D1A") (pin "2") (pinfunction "2_2") (pintype "passive"))
      (node (ref "D3") (pin "2") (pinfunction "2_2") (pintype "passive"))
      (node (ref "GND") (pin "1") (pinfunction "1_1") (pintype "passive"))
      (node (ref "R11") (pin "1") (pinfunction "1_1") (pintype "passive"))
      (node (ref "R16") (pin "2") (pinfunction "2_2") (pintype "passive"))
      (node (ref "R17") (pin "1") (pinfunction "1_1") (pintype "passive"))
      (node (ref "R20") (pin "2") (pinfunction "2_2") (pintype "passive"))
      (node (ref "R22") (pin "2") (pinfunction "2_2") (pintype "passive"))
      (node (ref "R23") (pin "2") (pinfunction "2_2") (pintype "passive"))
      (node (ref "R24") (pin "1") (pinfunction "1_1") (pintype "passive"))
      (node (ref "R25") (pin "1") (pinfunction "1_1") (pintype "passive"))
      (node (ref "R7") (pin "1") (pinfunction "1_1") (pintype "passive"))
      (node (ref "R8") (pin "1") (pinfunction "1_1") (pintype "passive"))
      (node (ref "U1") (pin "7") (pinfunction "GND_7") (pintype "passive"))
      (node (ref "U2") (pin "4") (pinfunction "GND_4") (pintype "passive"))
      (node (ref "U3") (pin "2") (pinfunction "GND_2") (pintype "passive"))
      (node (ref "U4") (pin "4") (pinfunction "GND_4") (pintype "passive"))
      (node (ref "X1") (pin "5") (pinfunction "5_5") (pintype "passive"))
      (node (ref "X1") (pin "6") (pinfunction "6_6") (pintype "passive"))
      (node (ref "X1") (pin "7") (pinfunction "7_7") (pintype "passive"))
      (node (ref "X1") (pin "9") (pinfunction "9_9") (pintype "passive"))
      (node (ref "X2") (pin "4") (pinfunction "4_4") (pintype "passive"))
      (node (ref "X2") (pin "6") (pinfunction "6_6") (pintype "passive"))
      (node (ref "X2") (pin "7") (pinfunction "7_7") (pintype "passive"))
      (node (ref "X2") (pin "8") (pinfunction "8_8") (pintype "passive"))
    )
    (net (code "23") (name "Net-(C12-Pad1)") (class "Default")
      (node (ref "C12") (pin "1") (pinfunction "1_1") (pintype "passive"))
      (node (ref "D5") (pin "2") (pinfunction "2_2") (pintype "passive"))
      (node (ref "R32") (pin "1") (pinfunction "1_1") (pintype "passive"))
      (node (ref "R33") (pin "2") (pinfunction "2_2") (pintype "passive"))
      (node (ref "R34") (pin "1") (pinfunction "1_1") (pintype "passive"))
    )
    (net (code "24") (name "Net-(C13-Pad2)") (class "Default")
      (node (ref "C13") (pin "2") (pinfunction "2_2") (pintype "passive"))
      (node (ref "D7") (pin "2") (pinfunction "2_2") (pintype "passive"))
      (node (ref "R38") (pin "2") (pinfunction "2_2") (pintype "passive"))
      (node (ref "R39") (pin "1") (pinfunction "1_1") (pintype "passive"))
      (node (ref "R40") (pin "2") (pinfunction "2_2") (pintype "passive"))
    )
    (net (code "25") (name "Net-(D2-A)") (class "Default")
      (node (ref "D2") (pin "1") (pinfunction "A_1") (pintype "passive"))
      (node (ref "JP1") (pin "2") (pinfunction "2_2") (pintype "passive"))
    )
    (net (code "26") (name "Net-(D6-Pad1)") (class "Default")
      (node (ref "D6") (pin "1") (pinfunction "1_1") (pintype "passive"))
      (node (ref "R37") (pin "1") (pinfunction "1_1") (pintype "passive"))
    )
    (net (code "27") (name "Net-(D8-Pad1)") (class "Default")
      (node (ref "D8") (pin "1") (pinfunction "1_1") (pintype "passive"))
      (node (ref "R43") (pin "1") (pinfunction "1_1") (pintype "passive"))
    )
    (net (code "28") (name "Net-(D9-Pad2)") (class "Default")
      (node (ref "D9") (pin "2") (pinfunction "2_2") (pintype "passive"))
      (node (ref "R33") (pin "1") (pinfunction "1_1") (pintype "passive"))
    )
    (net (code "29") (name "Net-(D10-Pad1)") (class "Default")
      (node (ref "D10") (pin "1") (pinfunction "1_1") (pintype "passive"))
      (node (ref "J1") (pin "1") (pinfunction "1_1") (pintype "passive"))
      (node (ref "J1") (pin "2") (pinfunction "2_2") (pintype "passive"))
    )
    (net (code "30") (name "Net-(D10-Pad2)") (class "Default")
      (node (ref "D10") (pin "2") (pinfunction "2_2") (pintype "passive"))
      (node (ref "D9") (pin "1") (pinfunction "1_1") (pintype "passive"))
    )
    (net (code "31") (name "Net-(D11-Pad2)") (class "Default")
      (node (ref "D11") (pin "2") (pinfunction "2_2") (pintype "passive"))
      (node (ref "J4") (pin "1") (pinfunction "1_1") (pintype "passive"))
      (node (ref "R41") (pin "2") (pinfunction "2_2") (pintype "passive"))
      (node (ref "R43") (pin "2") (pinfunction "2_2") (pintype "passive"))
    )
    (net (code "32") (name "Net-(D12-Pad2)") (class "Default")
      (node (ref "D12") (pin "2") (pinfunction "2_2") (pintype "passive"))
      (node (ref "J2") (pin "2") (pinfunction "2_2") (pintype "passive"))
      (node (ref "R35") (pin "2") (pinfunction "2_2") (pintype "passive"))
      (node (ref "R37") (pin "2") (pinfunction "2_2") (pintype "passive"))
    )
    (net (code "33") (name "Net-(D13-Pad1)") (class "Default")
      (node (ref "D13") (pin "1") (pinfunction "1_1") (pintype "passive"))
      (node (ref "D14") (pin "2") (pinfunction "2_2") (pintype "passive"))
    )
    (net (code "34") (name "Net-(D13-Pad2)") (class "Default")
      (node (ref "D13") (pin "2") (pinfunction "2_2") (pintype "passive"))
      (node (ref "R39") (pin "2") (pinfunction "2_2") (pintype "passive"))
    )
    (net (code "35") (name "Net-(D14-Pad1)") (class "Default")
      (node (ref "D14") (pin "1") (pinfunction "1_1") (pintype "passive"))
      (node (ref "J3") (pin "1") (pinfunction "1_1") (pintype "passive"))
      (node (ref "J3") (pin "2") (pinfunction "2_2") (pintype "passive"))
    )
    (net (code "36") (name "Net-(ERROR-K)") (class "Default")
      (node (ref "ERROR") (pin "2") (pinfunction "K_2") (pintype "passive"))
      (node (ref "R24") (pin "2") (pinfunction "2_2") (pintype "passive"))
    )
    (net (code "37") (name "Net-(PASS-K)") (class "Default")
      (node (ref "PASS") (pin "2") (pinfunction "K_2") (pintype "passive"))
      (node (ref "R16") (pin "1") (pinfunction "1_1") (pintype "passive"))
    )
    (net (code "38") (name "Net-(PWM-B-A)") (class "Default")
      (node (ref "PWM-B") (pin "1") (pinfunction "A_1") (pintype "passive"))
      (node (ref "R30") (pin "1") (pinfunction "1_1") (pintype "passive"))
    )
    (net (code "39") (name "Net-(PWM-T-A)") (class "Default")
      (node (ref "PWM-T") (pin "1") (pinfunction "A_1") (pintype "passive"))
      (node (ref "R29") (pin "2") (pinfunction "2_2") (pintype "passive"))
    )
    (net (code "40") (name "Net-(Q1-Pad2)") (class "Default")
      (node (ref "Q1") (pin "2") (pinfunction "2_2") (pintype "passive"))
      (node (ref "R22") (pin "1") (pinfunction "1_1") (pintype "passive"))
    )
    (net (code "41") (name "Net-(Q1-Pad3)") (class "Default")
      (node (ref "Q1") (pin "3") (pinfunction "3_3") (pintype "passive"))
      (node (ref "R18") (pin "2") (pinfunction "2_2") (pintype "passive"))
    )
    (net (code "42") (name "Net-(Q2-Pad1)") (class "Default")
      (node (ref "Q2") (pin "1") (pinfunction "1_1") (pintype "passive"))
      (node (ref "R21") (pin "1") (pinfunction "1_1") (pintype "passive"))
      (node (ref "R23") (pin "1") (pinfunction "1_1") (pintype "passive"))
    )
    (net (code "43") (name "Net-(Q2-Pad2)") (class "Default")
      (node (ref "Q2") (pin "2") (pinfunction "2_2") (pintype "passive"))
      (node (ref "R25") (pin "2") (pinfunction "2_2") (pintype "passive"))
    )
    (net (code "44") (name "Net-(Q3-Pad1)") (class "Default")
      (node (ref "Q3") (pin "1") (pinfunction "1_1") (pintype "passive"))
      (node (ref "R26") (pin "1") (pinfunction "1_1") (pintype "passive"))
    )
    (net (code "45") (name "Net-(Q3-Pad2)") (class "Default")
      (node (ref "Q3") (pin "2") (pinfunction "2_2") (pintype "passive"))
      (node (ref "R29") (pin "1") (pinfunction "1_1") (pintype "passive"))
    )
    (net (code "46") (name "Net-(Q4-Pad1)") (class "Default")
      (node (ref "Q4") (pin "1") (pinfunction "1_1") (pintype "passive"))
      (node (ref "R27") (pin "1") (pinfunction "1_1") (pintype "passive"))
    )
    (net (code "47") (name "Net-(Q4-Pad2)") (class "Default")
      (node (ref "Q4") (pin "2") (pinfunction "2_2") (pintype "passive"))
      (node (ref "R30") (pin "2") (pinfunction "2_2") (pintype "passive"))
    )
    (net (code "48") (name "Net-(R5-Pad2)") (class "Default")
      (node (ref "R5") (pin "2") (pinfunction "2_2") (pintype "passive"))
      (node (ref "R6") (pin "2") (pinfunction "2_2") (pintype "passive"))
    )
    (net (code "49") (name "Net-(U1-I{slash}P_B)") (class "Default")
      (node (ref "C10") (pin "2") (pinfunction "2_2") (pintype "passive"))
      (node (ref "R10") (pin "1") (pinfunction "1_1") (pintype "passive"))
      (node (ref "U1") (pin "3") (pinfunction "I/P_B_3") (pintype "passive"))
    )
    (net (code "50") (name "Net-(U1-I{slash}P_E)") (class "Default")
      (node (ref "C5") (pin "1") (pinfunction "1_1") (pintype "passive"))
      (node (ref "R15") (pin "2") (pinfunction "2_2") (pintype "passive"))
      (node (ref "U1") (pin "11") (pinfunction "I/P_E_11") (pintype "passive"))
    )
    (net (code "51") (name "Net-(U1-O{slash}P_A)") (class "Default")
      (node (ref "R10") (pin "2") (pinfunction "2_2") (pintype "passive"))
      (node (ref "U1") (pin "2") (pinfunction "O/P_A_2") (pintype "passive"))
    )
    (net (code "52") (name "Net-(U1-O{slash}P_C)") (class "Default")
      (node (ref "C10") (pin "1") (pinfunction "1_1") (pintype "passive"))
      (node (ref "U1") (pin "6") (pinfunction "O/P_C_6") (pintype "passive"))
    )
    (net (code "53") (name "Net-(U1-O{slash}P_D)") (class "Default")
      (node (ref "R15") (pin "1") (pinfunction "1_1") (pintype "passive"))
      (node (ref "U1") (pin "8") (pinfunction "O/P_D_8") (pintype "passive"))
    )
    (net (code "54") (name "Net-(U1-O{slash}P_F)") (class "Default")
      (node (ref "C5") (pin "2") (pinfunction "2_2") (pintype "passive"))
      (node (ref "U1") (pin "12") (pinfunction "O/P_F_12") (pintype "passive"))
    )
    (net (code "55") (name "Net-(U2-Drive_C)") (class "Default")
      (node (ref "R1") (pin "2") (pinfunction "2_2") (pintype "passive"))
      (node (ref "R2") (pin "2") (pinfunction "2_2") (pintype "passive"))
      (node (ref "R3") (pin "2") (pinfunction "2_2") (pintype "passive"))
      (node (ref "R4") (pin "2") (pinfunction "2_2") (pintype "passive"))
      (node (ref "U2") (pin "1") (pinfunction "Switch_C_1") (pintype "passive"))
      (node (ref "U2") (pin "7") (pinfunction "Peak_Sense_7") (pintype "passive"))
      (node (ref "U2") (pin "8") (pinfunction "Drive_C_8") (pintype "passive"))
    )
    (net (code "56") (name "Net-(U2-Inverting_I{slash}P)") (class "Default")
      (node (ref "R6") (pin "1") (pinfunction "1_1") (pintype "passive"))
      (node (ref "R8") (pin "2") (pinfunction "2_2") (pintype "passive"))
      (node (ref "U2") (pin "5") (pinfunction "Inverting_I/P_5") (pintype "passive"))
    )
    (net (code "57") (name "Net-(U2-Switch_E)") (class "Default")
      (node (ref "D1") (pin "1") (pinfunction "1_1") (pintype "passive"))
      (node (ref "D1A") (pin "1") (pinfunction "1_1") (pintype "passive"))
      (node (ref "L1") (pin "2") (pinfunction "2_2") (pintype "passive"))
      (node (ref "U2") (pin "2") (pinfunction "Switch_E_2") (pintype "passive"))
    )
    (net (code "58") (name "Net-(U2-Timmimg_Cap)") (class "Default")
      (node (ref "C2") (pin "2") (pinfunction "2_2") (pintype "passive"))
      (node (ref "C3") (pin "2") (pinfunction "2_2") (pintype "passive"))
      (node (ref "U2") (pin "3") (pinfunction "Timmimg_Cap_3") (pintype "passive"))
    )
    (net (code "59") (name "Net-(U4-TB)") (class "Default")
      (node (ref "R7") (pin "2") (pinfunction "2_2") (pintype "passive"))
      (node (ref "U4") (pin "1") (pinfunction "TB_1") (pintype "passive"))
    )
    (net (code "60") (name "unconnected-(M1-Pad1)") (class "Default")
      (node (ref "M1") (pin "1") (pinfunction "1_1") (pintype "passive"))
    )
    (net (code "61") (name "unconnected-(M2-Pad1)") (class "Default")
      (node (ref "M2") (pin "1") (pinfunction "1_1") (pintype "passive"))
    )
    (net (code "62") (name "unconnected-(M3-Pad1)") (class "Default")
      (node (ref "M3") (pin "1") (pinfunction "1_1") (pintype "passive"))
    )
    (net (code "63") (name "unconnected-(M4-Pad1)") (class "Default")
      (node (ref "M4") (pin "1") (pinfunction "1_1") (pintype "passive"))
    )
    (net (code "64") (name "unconnected-(X1-Pad3)") (class "Default")
      (node (ref "X1") (pin "3") (pinfunction "3_3") (pintype "passive"))
    )
    (net (code "65") (name "unconnected-(X1-Pad8)") (class "Default")
      (node (ref "X1") (pin "8") (pinfunction "8_8") (pintype "passive"))
    )
    (net (code "66") (name "unconnected-(X2-Pad5)") (class "Default")
      (node (ref "X2") (pin "5") (pinfunction "5_5") (pintype "passive"))
    )
    (net (code "67") (name "unconnected-(X2-Pad10)") (class "Default")
      (node (ref "X2") (pin "10") (pinfunction "10_10") (pintype "passive"))
    )
  )
)
